# Embedded_Circuits.net
KiCad netlist of a schematic drawn in Altium Designer
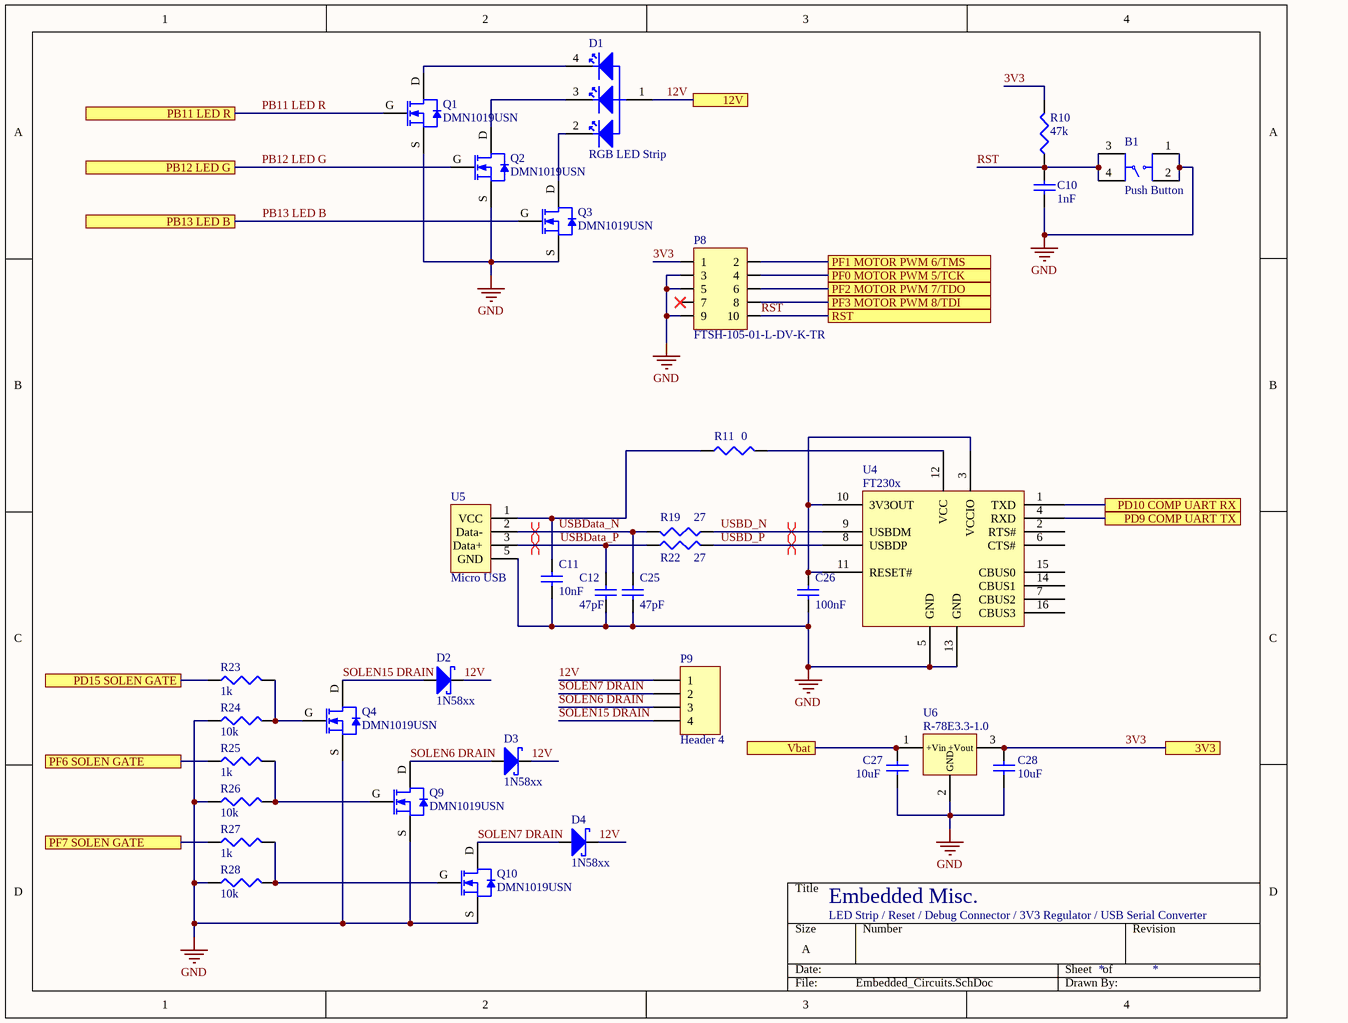
[diagram p0: Embedded_Circuits.SchDoc]

(export (version "E")
  (design (tool "Eeschema 10.0.6"))
  (components
    (comp (ref "B1")
      (value "Push Button")
      (footprint "Push Button")
      (description "Tactile Switch SPST-NO Top Actuated Through Hole")
      (libsource (lib "Power_Embedded_Board_Library") (part "Push Button"))
    )
    (comp (ref "C10")
      (value "1nF")
      (footprint "C1206")
      (description "Capacitor (Semiconductor SIM Model)")
      (fields (field (name "Comment") "Cap Semi") (field (name "PUBLISHER") "Altium Limited"))
      (libsource (lib "Miscellaneous Devices") (part "Cap Semi"))
    )
    (comp (ref "C11")
      (value "10nF")
      (footprint "C1206")
      (description "Capacitor")
      (fields (field (name "Comment") "Cap") (field (name "PUBLISHER") "Altium Limited"))
      (libsource (lib "Miscellaneous Devices") (part "Cap"))
    )
    (comp (ref "C12")
      (value "47pF")
      (footprint "C1206")
      (description "Capacitor")
      (fields (field (name "Comment") "Cap") (field (name "PUBLISHER") "Altium Limited"))
      (libsource (lib "Miscellaneous Devices") (part "Cap"))
    )
    (comp (ref "C25")
      (value "47pF")
      (footprint "C1206")
      (description "Capacitor")
      (fields (field (name "Comment") "Cap") (field (name "PUBLISHER") "Altium Limited"))
      (libsource (lib "Miscellaneous Devices") (part "Cap"))
    )
    (comp (ref "C26")
      (value "100nF")
      (footprint "C1206")
      (description "Capacitor")
      (fields (field (name "Comment") "Cap") (field (name "PUBLISHER") "Altium Limited"))
      (libsource (lib "Miscellaneous Devices") (part "Cap"))
    )
    (comp (ref "C27")
      (value "10uF")
      (footprint "C1206")
      (description "Capacitor")
      (fields (field (name "Comment") "Cap") (field (name "PUBLISHER") "Altium Limited"))
      (libsource (lib "Miscellaneous Devices") (part "Cap"))
    )
    (comp (ref "C28")
      (value "10uF")
      (footprint "C1206")
      (description "Capacitor")
      (fields (field (name "Comment") "Cap") (field (name "PUBLISHER") "Altium Limited"))
      (libsource (lib "Miscellaneous Devices") (part "Cap"))
    )
    (comp (ref "D1")
      (value "RGB LED Strip")
      (footprint "Header 1x4")
      (description "LED RGB Strip - Bare Nonaddressable")
      (libsource (lib "Power_Embedded_Board_Library") (part "RGB LED Strip"))
    )
    (comp (ref "D2")
      (value "1N58xx")
      (footprint "1N58xx")
      (description "1A Schottky Barrier Rectifier Diode")
      (libsource (lib "Power_Embedded_Board_Library") (part "1N58xx"))
    )
    (comp (ref "D3")
      (value "1N58xx")
      (footprint "1N58xx")
      (description "1A Schottky Barrier Rectifier Diode")
      (libsource (lib "Power_Embedded_Board_Library") (part "1N58xx"))
    )
    (comp (ref "D4")
      (value "1N58xx")
      (footprint "1N58xx")
      (description "1A Schottky Barrier Rectifier Diode")
      (libsource (lib "Power_Embedded_Board_Library") (part "1N58xx"))
    )
    (comp (ref "P8")
      (value "FTSH-105-01-L-DV-K-TR")
      (footprint "FTSH-105-01-L-DV-K-TR")
      (description "CONN HEADER 10POS DUAL .05\" SMD")
      (libsource (lib "Power_Embedded_Board_Library") (part "JTAG Header"))
    )
    (comp (ref "P9")
      (value "Header 4")
      (footprint "HDR1X4")
      (description "Header, 4-Pin")
      (fields (field (name "PUBLISHER") "Altium Limited"))
      (libsource (lib "Miscellaneous Connectors") (part "Header 4"))
    )
    (comp (ref "Q1")
      (value "DMN1019USN")
      (footprint "SOT-23")
      (description "12V N-Channel Enhancement Mode MOSFET")
      (libsource (lib "Power_Embedded_Board_Library") (part "DMN1019USN"))
    )
    (comp (ref "Q2")
      (value "DMN1019USN")
      (footprint "SOT-23")
      (description "12V N-Channel Enhancement Mode MOSFET")
      (libsource (lib "Power_Embedded_Board_Library") (part "DMN1019USN"))
    )
    (comp (ref "Q3")
      (value "DMN1019USN")
      (footprint "SOT-23")
      (description "12V N-Channel Enhancement Mode MOSFET")
      (libsource (lib "Power_Embedded_Board_Library") (part "DMN1019USN"))
    )
    (comp (ref "Q4")
      (value "DMN1019USN")
      (footprint "SOT-23")
      (description "12V N-Channel Enhancement Mode MOSFET")
      (libsource (lib "Power_Embedded_Board_Library") (part "DMN1019USN"))
    )
    (comp (ref "Q9")
      (value "DMN1019USN")
      (footprint "SOT-23")
      (description "12V N-Channel Enhancement Mode MOSFET")
      (libsource (lib "Power_Embedded_Board_Library") (part "DMN1019USN"))
    )
    (comp (ref "Q10")
      (value "DMN1019USN")
      (footprint "SOT-23")
      (description "12V N-Channel Enhancement Mode MOSFET")
      (libsource (lib "Power_Embedded_Board_Library") (part "DMN1019USN"))
    )
    (comp (ref "R10")
      (value "47k")
      (footprint "J1-0603")
      (description "Resistor")
      (fields (field (name "Comment") "Res3") (field (name "PUBLISHER") "Altium Limited"))
      (libsource (lib "Miscellaneous Devices") (part "Res3"))
    )
    (comp (ref "R11")
      (value "0")
      (footprint "J1-0603")
      (description "Resistor")
      (fields (field (name "Comment") "Res3") (field (name "PUBLISHER") "Altium Limited"))
      (libsource (lib "Miscellaneous Devices") (part "Res3"))
    )
    (comp (ref "R19")
      (value "27")
      (footprint "J1-0603")
      (description "Resistor")
      (fields (field (name "Comment") "Res3") (field (name "PUBLISHER") "Altium Limited"))
      (libsource (lib "Miscellaneous Devices") (part "Res3"))
    )
    (comp (ref "R22")
      (value "27")
      (footprint "J1-0603")
      (description "Resistor")
      (fields (field (name "Comment") "Res3") (field (name "PUBLISHER") "Altium Limited"))
      (libsource (lib "Miscellaneous Devices") (part "Res3"))
    )
    (comp (ref "R23")
      (value "1k")
      (footprint "J1-0603")
      (description "Resistor")
      (fields (field (name "Comment") "Res3") (field (name "PUBLISHER") "Altium Limited"))
      (libsource (lib "Miscellaneous Devices") (part "Res3"))
    )
    (comp (ref "R24")
      (value "10k")
      (footprint "J1-0603")
      (description "Resistor")
      (fields (field (name "Comment") "Res3") (field (name "PUBLISHER") "Altium Limited"))
      (libsource (lib "Miscellaneous Devices") (part "Res3"))
    )
    (comp (ref "R25")
      (value "1k")
      (footprint "J1-0603")
      (description "Resistor")
      (fields (field (name "Comment") "Res3") (field (name "PUBLISHER") "Altium Limited"))
      (libsource (lib "Miscellaneous Devices") (part "Res3"))
    )
    (comp (ref "R26")
      (value "10k")
      (footprint "J1-0603")
      (description "Resistor")
      (fields (field (name "Comment") "Res3") (field (name "PUBLISHER") "Altium Limited"))
      (libsource (lib "Miscellaneous Devices") (part "Res3"))
    )
    (comp (ref "R27")
      (value "1k")
      (footprint "J1-0603")
      (description "Resistor")
      (fields (field (name "Comment") "Res3") (field (name "PUBLISHER") "Altium Limited"))
      (libsource (lib "Miscellaneous Devices") (part "Res3"))
    )
    (comp (ref "R28")
      (value "10k")
      (footprint "J1-0603")
      (description "Resistor")
      (fields (field (name "Comment") "Res3") (field (name "PUBLISHER") "Altium Limited"))
      (libsource (lib "Miscellaneous Devices") (part "Res3"))
    )
    (comp (ref "U4")
      (value "FT230x")
      (footprint "FT230X")
      (description "USB to Basic UART IC")
      (libsource (lib "Power_Embedded_Board_Library") (part "FTDI FT230x"))
    )
    (comp (ref "U5")
      (value "Micro USB")
      (footprint "Micro USB")
      (description "USB - micro B USB 2.0 Receptacle Connector 5 Position Surface Mount, Right Angle")
      (libsource (lib "Power_Embedded_Board_Library") (part "Micro USB"))
    )
    (comp (ref "U6")
      (value "R-78E3.3-1.0")
      (footprint "R-78Exx-1.0")
      (description "1A DC/DC Voltage Converter")
      (libsource (lib "Power_Embedded_Board_Library") (part "R-78Exx-1.0"))
    )
  )
  (nets
    (net (code "1") (name "/3V3") (class "Default")
      (node (ref "C28") (pin "2") (pinfunction "2_2") (pintype "passive"))
      (node (ref "P8") (pin "1") (pinfunction "1_1") (pintype "passive"))
      (node (ref "R10") (pin "2") (pinfunction "2_2") (pintype "passive"))
      (node (ref "U6") (pin "3") (pinfunction "+Vout_3") (pintype "passive"))
    )
    (net (code "2") (name "/12V") (class "Default")
      (node (ref "D1") (pin "1") (pinfunction "1_1") (pintype "passive"))
      (node (ref "D2") (pin "K") (pinfunction "Cathode_K") (pintype "passive"))
      (node (ref "D3") (pin "K") (pinfunction "Cathode_K") (pintype "passive"))
      (node (ref "D4") (pin "K") (pinfunction "Cathode_K") (pintype "passive"))
      (node (ref "P9") (pin "1") (pinfunction "1_1") (pintype "passive"))
    )
    (net (code "3") (name "/PB11 LED R") (class "Default")
      (node (ref "Q1") (pin "G") (pinfunction "G_G") (pintype "passive"))
    )
    (net (code "4") (name "/PB12 LED G") (class "Default")
      (node (ref "Q2") (pin "G") (pinfunction "G_G") (pintype "passive"))
    )
    (net (code "5") (name "/PB13 LED B") (class "Default")
      (node (ref "Q3") (pin "G") (pinfunction "G_G") (pintype "passive"))
    )
    (net (code "6") (name "/PD9 COMP UART TX") (class "Default")
      (node (ref "U4") (pin "4") (pinfunction "RXD_4") (pintype "passive"))
    )
    (net (code "7") (name "/PD10 COMP UART RX") (class "Default")
      (node (ref "U4") (pin "1") (pinfunction "TXD_1") (pintype "passive"))
    )
    (net (code "8") (name "/PD15 SOLEN GATE") (class "Default")
      (node (ref "R23") (pin "1") (pinfunction "1_1") (pintype "passive"))
    )
    (net (code "9") (name "/PF0 MOTOR PWM 5{slash}TCK") (class "Default")
      (node (ref "P8") (pin "4") (pinfunction "4_4") (pintype "passive"))
    )
    (net (code "10") (name "/PF1 MOTOR PWM 6{slash}TMS") (class "Default")
      (node (ref "P8") (pin "2") (pinfunction "2_2") (pintype "passive"))
    )
    (net (code "11") (name "/PF2 MOTOR PWM 7{slash}TDO") (class "Default")
      (node (ref "P8") (pin "6") (pinfunction "6_6") (pintype "passive"))
    )
    (net (code "12") (name "/PF3 MOTOR PWM 8{slash}TDI") (class "Default")
      (node (ref "P8") (pin "8") (pinfunction "8_8") (pintype "passive"))
    )
    (net (code "13") (name "/PF6 SOLEN GATE") (class "Default")
      (node (ref "R25") (pin "1") (pinfunction "1_1") (pintype "passive"))
    )
    (net (code "14") (name "/PF7 SOLEN GATE") (class "Default")
      (node (ref "R27") (pin "1") (pinfunction "1_1") (pintype "passive"))
    )
    (net (code "15") (name "/RST") (class "Default")
      (node (ref "B1") (pin "3") (pinfunction "3_3") (pintype "passive"))
      (node (ref "B1") (pin "4") (pinfunction "4_4") (pintype "passive"))
      (node (ref "C10") (pin "2") (pinfunction "2_2") (pintype "passive"))
      (node (ref "P8") (pin "10") (pinfunction "10_10") (pintype "passive"))
      (node (ref "R10") (pin "1") (pinfunction "1_1") (pintype "passive"))
    )
    (net (code "16") (name "/SOLEN6 DRAIN") (class "Default")
      (node (ref "D3") (pin "A") (pinfunction "Anode_A") (pintype "passive"))
      (node (ref "P9") (pin "3") (pinfunction "3_3") (pintype "passive"))
      (node (ref "Q9") (pin "D") (pinfunction "D_D") (pintype "passive"))
    )
    (net (code "17") (name "/SOLEN7 DRAIN") (class "Default")
      (node (ref "D4") (pin "A") (pinfunction "Anode_A") (pintype "passive"))
      (node (ref "P9") (pin "2") (pinfunction "2_2") (pintype "passive"))
      (node (ref "Q10") (pin "D") (pinfunction "D_D") (pintype "passive"))
    )
    (net (code "18") (name "/SOLEN15 DRAIN") (class "Default")
      (node (ref "D2") (pin "A") (pinfunction "Anode_A") (pintype "passive"))
      (node (ref "P9") (pin "4") (pinfunction "4_4") (pintype "passive"))
      (node (ref "Q4") (pin "D") (pinfunction "D_D") (pintype "passive"))
    )
    (net (code "19") (name "/USBD_N") (class "Default")
      (node (ref "R19") (pin "1") (pinfunction "1_1") (pintype "passive"))
      (node (ref "U4") (pin "9") (pinfunction "USBDM_9") (pintype "passive"))
    )
    (net (code "20") (name "/USBD_P") (class "Default")
      (node (ref "R22") (pin "2") (pinfunction "2_2") (pintype "passive"))
      (node (ref "U4") (pin "8") (pinfunction "USBDP_8") (pintype "passive"))
    )
    (net (code "21") (name "/USBData_N") (class "Default")
      (node (ref "C25") (pin "2") (pinfunction "2_2") (pintype "passive"))
      (node (ref "R19") (pin "2") (pinfunction "2_2") (pintype "passive"))
      (node (ref "U5") (pin "2") (pinfunction "Data-_2") (pintype "passive"))
    )
    (net (code "22") (name "/USBData_P") (class "Default")
      (node (ref "C12") (pin "2") (pinfunction "2_2") (pintype "passive"))
      (node (ref "R22") (pin "1") (pinfunction "1_1") (pintype "passive"))
      (node (ref "U5") (pin "3") (pinfunction "Data+_3") (pintype "passive"))
    )
    (net (code "23") (name "/Vbat") (class "Default")
      (node (ref "C27") (pin "2") (pinfunction "2_2") (pintype "passive"))
      (node (ref "U6") (pin "1") (pinfunction "+Vin_1") (pintype "passive"))
    )
    (net (code "24") (name "GND") (class "Default")
      (node (ref "B1") (pin "1") (pinfunction "1_1") (pintype "passive"))
      (node (ref "B1") (pin "2") (pinfunction "2_2") (pintype "passive"))
      (node (ref "C10") (pin "1") (pinfunction "1_1") (pintype "passive"))
      (node (ref "C11") (pin "1") (pinfunction "1_1") (pintype "passive"))
      (node (ref "C12") (pin "1") (pinfunction "1_1") (pintype "passive"))
      (node (ref "C25") (pin "1") (pinfunction "1_1") (pintype "passive"))
      (node (ref "C26") (pin "1") (pinfunction "1_1") (pintype "passive"))
      (node (ref "C27") (pin "1") (pinfunction "1_1") (pintype "passive"))
      (node (ref "C28") (pin "1") (pinfunction "1_1") (pintype "passive"))
      (node (ref "P8") (pin "3") (pinfunction "3_3") (pintype "passive"))
      (node (ref "P8") (pin "5") (pinfunction "5_5") (pintype "passive"))
      (node (ref "P8") (pin "9") (pinfunction "9_9") (pintype "passive"))
      (node (ref "Q1") (pin "S") (pinfunction "S_S") (pintype "passive"))
      (node (ref "Q10") (pin "S") (pinfunction "S_S") (pintype "passive"))
      (node (ref "Q2") (pin "S") (pinfunction "S_S") (pintype "passive"))
      (node (ref "Q3") (pin "S") (pinfunction "S_S") (pintype "passive"))
      (node (ref "Q4") (pin "S") (pinfunction "S_S") (pintype "passive"))
      (node (ref "Q9") (pin "S") (pinfunction "S_S") (pintype "passive"))
      (node (ref "R24") (pin "1") (pinfunction "1_1") (pintype "passive"))
      (node (ref "R26") (pin "1") (pinfunction "1_1") (pintype "passive"))
      (node (ref "R28") (pin "1") (pinfunction "1_1") (pintype "passive"))
      (node (ref "U4") (pin "13") (pinfunction "GND_13") (pintype "passive"))
      (node (ref "U4") (pin "5") (pinfunction "GND_5") (pintype "passive"))
      (node (ref "U5") (pin "5") (pinfunction "GND_5") (pintype "passive"))
      (node (ref "U6") (pin "2") (pinfunction "GND_2") (pintype "passive"))
    )
    (net (code "25") (name "Net-(D1-Pad2)") (class "Default")
      (node (ref "D1") (pin "2") (pinfunction "2_2") (pintype "passive"))
      (node (ref "Q3") (pin "D") (pinfunction "D_D") (pintype "passive"))
    )
    (net (code "26") (name "Net-(D1-Pad3)") (class "Default")
      (node (ref "D1") (pin "3") (pinfunction "3_3") (pintype "passive"))
      (node (ref "Q2") (pin "D") (pinfunction "D_D") (pintype "passive"))
    )
    (net (code "27") (name "Net-(D1-Pad4)") (class "Default")
      (node (ref "D1") (pin "4") (pinfunction "4_4") (pintype "passive"))
      (node (ref "Q1") (pin "D") (pinfunction "D_D") (pintype "passive"))
    )
    (net (code "28") (name "Net-(Q4-PadG)") (class "Default")
      (node (ref "Q4") (pin "G") (pinfunction "G_G") (pintype "passive"))
      (node (ref "R23") (pin "2") (pinfunction "2_2") (pintype "passive"))
      (node (ref "R24") (pin "2") (pinfunction "2_2") (pintype "passive"))
    )
    (net (code "29") (name "Net-(Q9-PadG)") (class "Default")
      (node (ref "Q9") (pin "G") (pinfunction "G_G") (pintype "passive"))
      (node (ref "R25") (pin "2") (pinfunction "2_2") (pintype "passive"))
      (node (ref "R26") (pin "2") (pinfunction "2_2") (pintype "passive"))
    )
    (net (code "30") (name "Net-(Q10-PadG)") (class "Default")
      (node (ref "Q10") (pin "G") (pinfunction "G_G") (pintype "passive"))
      (node (ref "R27") (pin "2") (pinfunction "2_2") (pintype "passive"))
      (node (ref "R28") (pin "2") (pinfunction "2_2") (pintype "passive"))
    )
    (net (code "31") (name "Net-(U4-3V3OUT)") (class "Default")
      (node (ref "C26") (pin "2") (pinfunction "2_2") (pintype "passive"))
      (node (ref "U4") (pin "10") (pinfunction "3V3OUT_10") (pintype "passive"))
      (node (ref "U4") (pin "11") (pinfunction "RESET#_11") (pintype "passive"))
      (node (ref "U4") (pin "3") (pinfunction "VCCIO_3") (pintype "passive"))
    )
    (net (code "32") (name "Net-(U4-VCC)") (class "Default")
      (node (ref "R11") (pin "2") (pinfunction "2_2") (pintype "passive"))
      (node (ref "U4") (pin "12") (pinfunction "VCC_12") (pintype "passive"))
    )
    (net (code "33") (name "Net-(U5-VCC)") (class "Default")
      (node (ref "C11") (pin "2") (pinfunction "2_2") (pintype "passive"))
      (node (ref "R11") (pin "1") (pinfunction "1_1") (pintype "passive"))
      (node (ref "U5") (pin "1") (pinfunction "VCC_1") (pintype "passive"))
    )
    (net (code "34") (name "unconnected-(P8-Pad7)") (class "Default")
      (node (ref "P8") (pin "7") (pinfunction "7_7") (pintype "passive+no_connect"))
    )
    (net (code "35") (name "unconnected-(U4-CBUS0-Pad15)") (class "Default")
      (node (ref "U4") (pin "15") (pinfunction "CBUS0_15") (pintype "passive"))
    )
    (net (code "36") (name "unconnected-(U4-CBUS1-Pad14)") (class "Default")
      (node (ref "U4") (pin "14") (pinfunction "CBUS1_14") (pintype "passive"))
    )
    (net (code "37") (name "unconnected-(U4-CBUS2-Pad7)") (class "Default")
      (node (ref "U4") (pin "7") (pinfunction "CBUS2_7") (pintype "passive"))
    )
    (net (code "38") (name "unconnected-(U4-CBUS3-Pad16)") (class "Default")
      (node (ref "U4") (pin "16") (pinfunction "CBUS3_16") (pintype "passive"))
    )
    (net (code "39") (name "unconnected-(U4-CTS#-Pad6)") (class "Default")
      (node (ref "U4") (pin "6") (pinfunction "CTS#_6") (pintype "passive"))
    )
    (net (code "40") (name "unconnected-(U4-RTS#-Pad2)") (class "Default")
      (node (ref "U4") (pin "2") (pinfunction "RTS#_2") (pintype "passive"))
    )
  )
)
